# stuff-BASIC.net
KiCad netlist of a schematic drawn in EAGLE
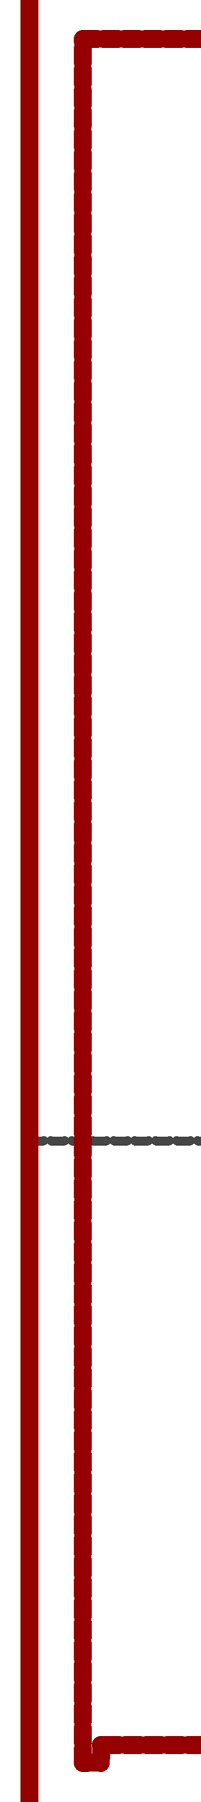
[diagram p0: schematic, sheet 1, part 1 of 2]
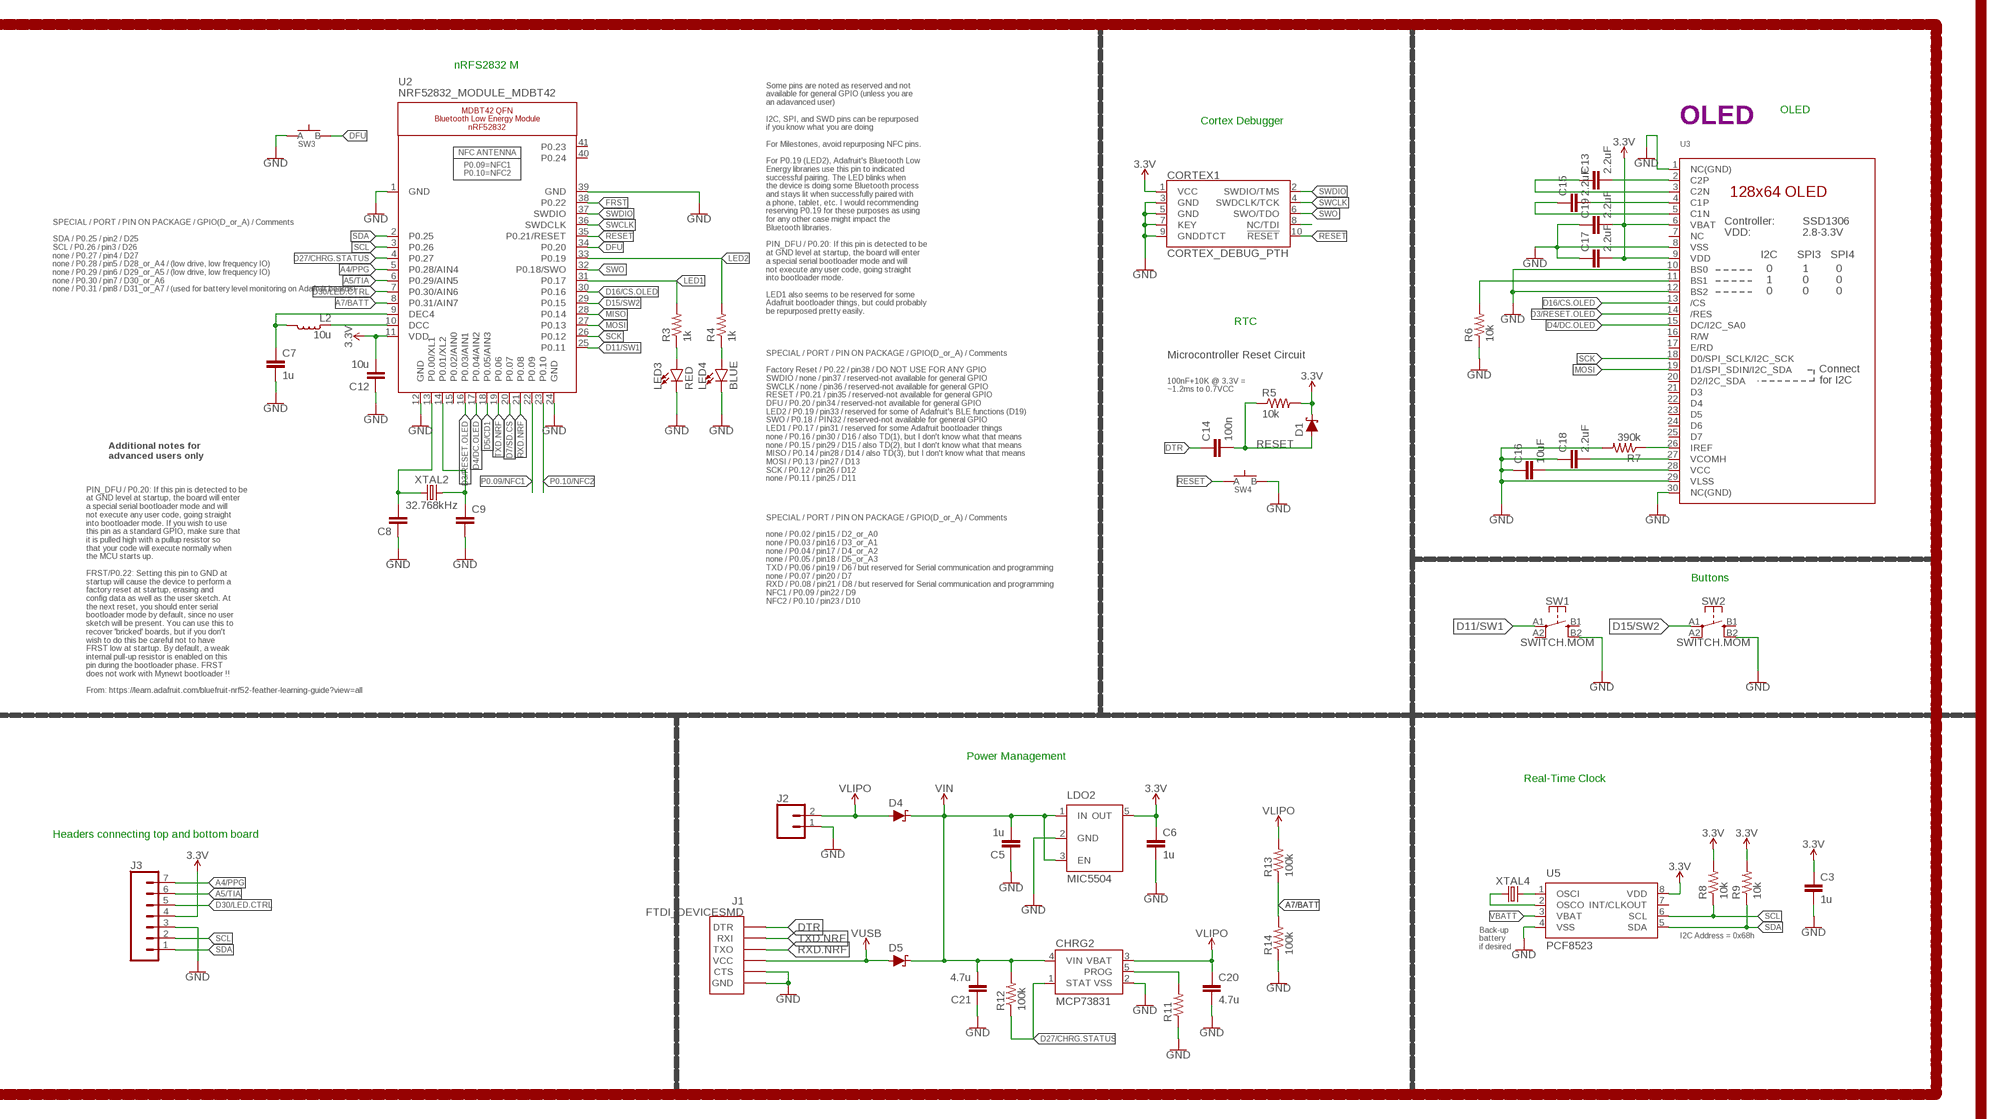
[diagram p1: schematic, sheet 1, part 2 of 2]

(export (version "E")
  (design (tool "Eeschema 10.0.6"))
  (components
    (comp (ref "C3")
      (value "1u")
      (footprint "eagle-import:C0603")
      (libsource (lib "eagle-import") (part "CAPACITOR0603"))
    )
    (comp (ref "C5")
      (value "1u")
      (footprint "eagle-import:C0603")
      (libsource (lib "eagle-import") (part "CAPACITOR0603"))
    )
    (comp (ref "C6")
      (value "1u")
      (footprint "eagle-import:C0603")
      (libsource (lib "eagle-import") (part "CAPACITOR0603"))
    )
    (comp (ref "C7")
      (value "1u")
      (footprint "eagle-import:C0603")
      (libsource (lib "eagle-import") (part "CAPACITOR0603"))
    )
    (comp (ref "C8")
      (value "CAPACITOR0603")
      (footprint "eagle-import:C0603")
      (libsource (lib "eagle-import") (part "CAPACITOR0603"))
    )
    (comp (ref "C9")
      (value "CAPACITOR0603")
      (footprint "eagle-import:C0603")
      (libsource (lib "eagle-import") (part "CAPACITOR0603"))
    )
    (comp (ref "C12")
      (value "10u")
      (footprint "eagle-import:C0805")
      (libsource (lib "eagle-import") (part "CAPACITOR0805"))
    )
    (comp (ref "C13")
      (value "2.2uF")
      (footprint "eagle-import:C0603")
      (libsource (lib "eagle-import") (part "CAPACITOR0603"))
    )
    (comp (ref "C14")
      (value "100n")
      (footprint "eagle-import:C0603")
      (libsource (lib "eagle-import") (part "CAPACITOR0603"))
    )
    (comp (ref "C15")
      (value "2.2uF")
      (footprint "eagle-import:C0603")
      (libsource (lib "eagle-import") (part "CAPACITOR0603"))
    )
    (comp (ref "C16")
      (value "10uF")
      (footprint "eagle-import:C0603")
      (libsource (lib "eagle-import") (part "CAPACITOR0603"))
    )
    (comp (ref "C17")
      (value "2.2uF")
      (footprint "eagle-import:C0603")
      (libsource (lib "eagle-import") (part "CAPACITOR0603"))
    )
    (comp (ref "C18")
      (value "2.2uF")
      (footprint "eagle-import:C0603")
      (libsource (lib "eagle-import") (part "CAPACITOR0603"))
    )
    (comp (ref "C19")
      (value "2.2uF")
      (footprint "eagle-import:C0603")
      (libsource (lib "eagle-import") (part "CAPACITOR0603"))
    )
    (comp (ref "C20")
      (value "4.7u")
      (footprint "eagle-import:C0603")
      (libsource (lib "eagle-import") (part "CAPACITOR0603"))
    )
    (comp (ref "C21")
      (value "4.7u")
      (footprint "eagle-import:C0603")
      (libsource (lib "eagle-import") (part "CAPACITOR0603"))
    )
    (comp (ref "CHRG2")
      (value "MCP73831")
      (footprint "eagle-import:SOT23-5")
      (libsource (lib "eagle-import") (part "MCP73831"))
    )
    (comp (ref "CORTEX1")
      (value "CORTEX_DEBUG_PTH")
      (footprint "eagle-import:2X5-PTH-1.27MM")
      (libsource (lib "eagle-import") (part "CORTEX_DEBUG_PTH"))
    )
    (comp (ref "D1")
      (value "SCHOTTKY-USC")
      (footprint "eagle-import:USC")
      (libsource (lib "eagle-import") (part "SCHOTTKY-USC"))
    )
    (comp (ref "D4")
      (value "SCHOTTKY-USC")
      (footprint "eagle-import:USC")
      (libsource (lib "eagle-import") (part "SCHOTTKY-USC"))
    )
    (comp (ref "D5")
      (value "SCHOTTKY-USC")
      (footprint "eagle-import:USC")
      (libsource (lib "eagle-import") (part "SCHOTTKY-USC"))
    )
    (comp (ref "J1")
      (value "FTDI_DEVICESMD")
      (footprint "eagle-import:FTDI-SMD")
      (libsource (lib "eagle-import") (part "FTDI_DEVICESMD"))
    )
    (comp (ref "J2")
      (value "CONN_02")
      (footprint "eagle-import:1X02")
      (libsource (lib "eagle-import") (part "CONN_02"))
    )
    (comp (ref "J3")
      (value "CONN_07-1.27MM")
      (footprint "eagle-import:1X07_1.27MM")
      (libsource (lib "eagle-import") (part "CONN_07-1.27MM"))
    )
    (comp (ref "L2")
      (value "10u")
      (footprint "eagle-import:L0603")
      (libsource (lib "eagle-import") (part "INDUCTOR0603"))
    )
    (comp (ref "LDO2")
      (value "MIC5504")
      (footprint "eagle-import:SOT23-5")
      (libsource (lib "eagle-import") (part "MIC5504"))
    )
    (comp (ref "LED3")
      (value "RED")
      (footprint "eagle-import:LED-0603")
      (libsource (lib "eagle-import") (part "LED0603"))
    )
    (comp (ref "LED4")
      (value "BLUE")
      (footprint "eagle-import:LED-0603")
      (libsource (lib "eagle-import") (part "LED0603"))
    )
    (comp (ref "R3")
      (value "1k")
      (footprint "eagle-import:R0603")
      (libsource (lib "eagle-import") (part "RESISTOR0603"))
    )
    (comp (ref "R4")
      (value "1k")
      (footprint "eagle-import:R0603")
      (libsource (lib "eagle-import") (part "RESISTOR0603"))
    )
    (comp (ref "R5")
      (value "10k")
      (footprint "eagle-import:R0603")
      (libsource (lib "eagle-import") (part "RESISTOR0603"))
    )
    (comp (ref "R6")
      (value "10k")
      (footprint "eagle-import:R0603")
      (libsource (lib "eagle-import") (part "RESISTOR0603"))
    )
    (comp (ref "R7")
      (value "390k")
      (footprint "eagle-import:R0603")
      (libsource (lib "eagle-import") (part "RESISTOR0603"))
    )
    (comp (ref "R8")
      (value "10k")
      (footprint "eagle-import:R0603")
      (libsource (lib "eagle-import") (part "RESISTOR0603"))
    )
    (comp (ref "R9")
      (value "10k")
      (footprint "eagle-import:R0603")
      (libsource (lib "eagle-import") (part "RESISTOR0603"))
    )
    (comp (ref "R11")
      (value "RESISTOR0603")
      (footprint "eagle-import:R0603")
      (libsource (lib "eagle-import") (part "RESISTOR0603"))
    )
    (comp (ref "R12")
      (value "100k")
      (footprint "eagle-import:R0603")
      (libsource (lib "eagle-import") (part "RESISTOR0603"))
    )
    (comp (ref "R13")
      (value "100k")
      (footprint "eagle-import:R0603")
      (libsource (lib "eagle-import") (part "RESISTOR0603"))
    )
    (comp (ref "R14")
      (value "100k")
      (footprint "eagle-import:R0603")
      (libsource (lib "eagle-import") (part "RESISTOR0603"))
    )
    (comp (ref "SW1")
      (value "SWITCH.MOM")
      (footprint "eagle-import:TACTILE_SWITCH_SMD_6.2MM_TALL")
      (libsource (lib "eagle-import") (part "SWITCH.MOM"))
    )
    (comp (ref "SW2")
      (value "SWITCH.MOM")
      (footprint "eagle-import:TACTILE_SWITCH_SMD_6.2MM_TALL")
      (libsource (lib "eagle-import") (part "SWITCH.MOM"))
    )
    (comp (ref "SW3")
      (value "SPST-PTS830GG140-COPY.1-3")
      (footprint "eagle-import:BUTTON-GULLWING")
      (libsource (lib "eagle-import") (part "SPST-PTS830GG140-COPY.1-3"))
    )
    (comp (ref "SW4")
      (value "SPST-PTS830GG140-COPY.1-3")
      (footprint "eagle-import:BUTTON-GULLWING")
      (libsource (lib "eagle-import") (part "SPST-PTS830GG140-COPY.1-3"))
    )
    (comp (ref "U2")
      (value "NRF52832_MODULE_MDBT42")
      (footprint "eagle-import:BLE_MODULE_RAYTAC_MDBT42")
      (libsource (lib "eagle-import") (part "NRF52832_MODULE_MDBT42"))
    )
    (comp (ref "U3")
      (value "DISP_OLED_UG-2864HSWEG01-NO-WRAPAROUND")
      (footprint "eagle-import:UG-2864HSWEG01_0.96IN_NO-WRAPAROUND")
      (libsource (lib "eagle-import") (part "DISP_OLED_UG-2864HSWEG01-NO-WRAPAROUND"))
    )
    (comp (ref "U5")
      (value "PCF8523")
      (footprint "eagle-import:SO8")
      (libsource (lib "eagle-import") (part "PCF8523"))
    )
    (comp (ref "XTAL2")
      (value "32.768kHz")
      (footprint "eagle-import:2-SMD.NOLEAD.2.0MMTO1.2MM")
      (libsource (lib "eagle-import") (part "CRYSTALECS-.327-12.5-12-C-TR"))
    )
    (comp (ref "XTAL4")
      (value "32.7680kHz")
      (footprint "eagle-import:2-SMD.NOLEAD.2.0MMTO1.2MM")
      (fields (field (name "FREQ") "32.7680KHZ"))
      (libsource (lib "eagle-import") (part "CRYSTALECS-.327-12.5-12-C-TR"))
    )
  )
  (nets
    (net (code "1") (name "3.3V") (class "Default")
      (node (ref "C12") (pin "2") (pinfunction "2_2") (pintype "passive"))
      (node (ref "C17") (pin "2") (pinfunction "2_2") (pintype "passive"))
      (node (ref "C19") (pin "2") (pinfunction "2_2") (pintype "passive"))
      (node (ref "C3") (pin "1") (pinfunction "1_1") (pintype "passive"))
      (node (ref "C6") (pin "1") (pinfunction "1_1") (pintype "passive"))
      (node (ref "CORTEX1") (pin "1") (pinfunction "VCC_1") (pintype "bidirectional"))
      (node (ref "D1") (pin "-") (pinfunction "C_-") (pintype "passive"))
      (node (ref "J3") (pin "4") (pinfunction "4_4") (pintype "passive"))
      (node (ref "LDO2") (pin "5") (pinfunction "OUT_5") (pintype "bidirectional"))
      (node (ref "R5") (pin "2") (pinfunction "2_2") (pintype "passive"))
      (node (ref "R8") (pin "2") (pinfunction "2_2") (pintype "passive"))
      (node (ref "R9") (pin "2") (pinfunction "2_2") (pintype "passive"))
      (node (ref "U2") (pin "11") (pinfunction "VDD_11") (pintype "bidirectional"))
      (node (ref "U3") (pin "6") (pinfunction "VBAT_6") (pintype "input"))
      (node (ref "U3") (pin "9") (pinfunction "VDD_9") (pintype "power_in"))
      (node (ref "U5") (pin "8") (pinfunction "VDD_8") (pintype "power_in"))
    )
    (net (code "2") (name "A4{slash}PPG") (class "Default")
      (node (ref "J3") (pin "7") (pinfunction "7_7") (pintype "passive"))
      (node (ref "U2") (pin "5") (pinfunction "P0.28/AIN4_5") (pintype "bidirectional"))
    )
    (net (code "3") (name "A5{slash}TIA") (class "Default")
      (node (ref "J3") (pin "6") (pinfunction "6_6") (pintype "passive"))
      (node (ref "U2") (pin "6") (pinfunction "P0.29/AIN5_6") (pintype "bidirectional"))
    )
    (net (code "4") (name "A7{slash}BATT") (class "Default")
      (node (ref "R13") (pin "1") (pinfunction "1_1") (pintype "passive"))
      (node (ref "R14") (pin "2") (pinfunction "2_2") (pintype "passive"))
      (node (ref "U2") (pin "8") (pinfunction "P0.31/AIN7_8") (pintype "bidirectional"))
    )
    (net (code "5") (name "D3{slash}RESET.OLED") (class "Default")
      (node (ref "U2") (pin "16") (pinfunction "P0.03/AIN1_16") (pintype "bidirectional"))
      (node (ref "U3") (pin "14") (pinfunction "/RES_14") (pintype "input"))
    )
    (net (code "6") (name "D4{slash}DC.OLED") (class "Default")
      (node (ref "U2") (pin "17") (pinfunction "P0.04/AIN2_17") (pintype "bidirectional"))
      (node (ref "U3") (pin "15") (pinfunction "DC/I2C_SA0_15") (pintype "input"))
    )
    (net (code "7") (name "D5{slash}CD1") (class "Default")
      (node (ref "U2") (pin "18") (pinfunction "P0.05/AIN3_18") (pintype "bidirectional"))
    )
    (net (code "8") (name "D7{slash}SD.CS") (class "Default")
      (node (ref "U2") (pin "20") (pinfunction "P0.07_20") (pintype "bidirectional"))
    )
    (net (code "9") (name "D11{slash}SW1") (class "Default")
      (node (ref "SW1") (pin "A1") (pinfunction "1_A1") (pintype "passive"))
      (node (ref "U2") (pin "25") (pinfunction "P0.11_25") (pintype "bidirectional"))
    )
    (net (code "10") (name "D15{slash}SW2") (class "Default")
      (node (ref "SW2") (pin "A1") (pinfunction "1_A1") (pintype "passive"))
      (node (ref "U2") (pin "29") (pinfunction "P0.15_29") (pintype "bidirectional"))
    )
    (net (code "11") (name "D16{slash}CS.OLED") (class "Default")
      (node (ref "U2") (pin "30") (pinfunction "P0.16_30") (pintype "bidirectional"))
      (node (ref "U3") (pin "13") (pinfunction "/CS_13") (pintype "input"))
    )
    (net (code "12") (name "D27{slash}CHRG.STATUS") (class "Default")
      (node (ref "CHRG2") (pin "1") (pinfunction "STAT_1") (pintype "output"))
      (node (ref "R12") (pin "1") (pinfunction "1_1") (pintype "passive"))
      (node (ref "U2") (pin "4") (pinfunction "P0.27_4") (pintype "bidirectional"))
    )
    (net (code "13") (name "D30{slash}LED.CTRL") (class "Default")
      (node (ref "J3") (pin "5") (pinfunction "5_5") (pintype "passive"))
      (node (ref "U2") (pin "7") (pinfunction "P0.30/AIN6_7") (pintype "bidirectional"))
    )
    (net (code "14") (name "DFU") (class "Default")
      (node (ref "SW3") (pin "3") (pinfunction "B_3") (pintype "bidirectional"))
      (node (ref "U2") (pin "34") (pinfunction "P0.20_34") (pintype "bidirectional"))
    )
    (net (code "15") (name "DTR") (class "Default")
      (node (ref "C14") (pin "1") (pinfunction "1_1") (pintype "passive"))
      (node (ref "J1") (pin "DTR") (pinfunction "DTR_DTR") (pintype "bidirectional"))
    )
    (net (code "16") (name "FRST") (class "Default")
      (node (ref "U2") (pin "38") (pinfunction "P0.22_38") (pintype "bidirectional"))
    )
    (net (code "17") (name "GND") (class "Default")
      (node (ref "C12") (pin "1") (pinfunction "1_1") (pintype "passive"))
      (node (ref "C16") (pin "1") (pinfunction "1_1") (pintype "passive"))
      (node (ref "C17") (pin "1") (pinfunction "1_1") (pintype "passive"))
      (node (ref "C18") (pin "1") (pinfunction "1_1") (pintype "passive"))
      (node (ref "C19") (pin "1") (pinfunction "1_1") (pintype "passive"))
      (node (ref "C20") (pin "2") (pinfunction "2_2") (pintype "passive"))
      (node (ref "C21") (pin "1") (pinfunction "1_1") (pintype "passive"))
      (node (ref "C3") (pin "2") (pinfunction "2_2") (pintype "passive"))
      (node (ref "C5") (pin "1") (pinfunction "1_1") (pintype "passive"))
      (node (ref "C6") (pin "2") (pinfunction "2_2") (pintype "passive"))
      (node (ref "C7") (pin "2") (pinfunction "2_2") (pintype "passive"))
      (node (ref "C8") (pin "1") (pinfunction "1_1") (pintype "passive"))
      (node (ref "C9") (pin "2") (pinfunction "2_2") (pintype "passive"))
      (node (ref "CHRG2") (pin "2") (pinfunction "VSS_2") (pintype "power_in"))
      (node (ref "CORTEX1") (pin "3") (pinfunction "GND_3") (pintype "bidirectional"))
      (node (ref "CORTEX1") (pin "5") (pinfunction "GND_5") (pintype "bidirectional"))
      (node (ref "CORTEX1") (pin "7") (pinfunction "KEY_7") (pintype "bidirectional"))
      (node (ref "CORTEX1") (pin "9") (pinfunction "GNDDTCT_9") (pintype "bidirectional"))
      (node (ref "J1") (pin "CTS") (pinfunction "CTS_CTS") (pintype "bidirectional"))
      (node (ref "J1") (pin "GND") (pinfunction "GND_GND") (pintype "bidirectional"))
      (node (ref "J2") (pin "1") (pinfunction "1_1") (pintype "passive"))
      (node (ref "J3") (pin "3") (pinfunction "3_3") (pintype "passive"))
      (node (ref "LDO2") (pin "2") (pinfunction "GND_2") (pintype "bidirectional"))
      (node (ref "LED3") (pin "C") (pinfunction "C_C") (pintype "passive"))
      (node (ref "LED4") (pin "C") (pinfunction "C_C") (pintype "passive"))
      (node (ref "R11") (pin "1") (pinfunction "1_1") (pintype "passive"))
      (node (ref "R14") (pin "1") (pinfunction "1_1") (pintype "passive"))
      (node (ref "R6") (pin "1") (pinfunction "1_1") (pintype "passive"))
      (node (ref "R7") (pin "2") (pinfunction "2_2") (pintype "passive"))
      (node (ref "SW1") (pin "B2") (pinfunction "4_B2") (pintype "passive"))
      (node (ref "SW2") (pin "B2") (pinfunction "4_B2") (pintype "passive"))
      (node (ref "SW3") (pin "1") (pinfunction "A_1") (pintype "bidirectional"))
      (node (ref "SW4") (pin "3") (pinfunction "B_3") (pintype "bidirectional"))
      (node (ref "U2") (pin "1") (pinfunction "GND_1") (pintype "bidirectional"))
      (node (ref "U2") (pin "12") (pinfunction "GND_12") (pintype "bidirectional"))
      (node (ref "U2") (pin "24") (pinfunction "GND_24") (pintype "bidirectional"))
      (node (ref "U2") (pin "39") (pinfunction "GND_39") (pintype "bidirectional"))
      (node (ref "U3") (pin "1") (pinfunction "NC(GND)_1") (pintype "input"))
      (node (ref "U3") (pin "10") (pinfunction "BS0_10") (pintype "input"))
      (node (ref "U3") (pin "12") (pinfunction "BS2_12") (pintype "input"))
      (node (ref "U3") (pin "29") (pinfunction "VLSS_29") (pintype "power_in"))
      (node (ref "U3") (pin "30") (pinfunction "NC(GND)_30") (pintype "input"))
      (node (ref "U3") (pin "8") (pinfunction "VSS_8") (pintype "power_in"))
      (node (ref "U5") (pin "4") (pinfunction "VSS_4") (pintype "power_in"))
    )
    (net (code "18") (name "LED1") (class "Default")
      (node (ref "R3") (pin "2") (pinfunction "2_2") (pintype "passive"))
      (node (ref "U2") (pin "31") (pinfunction "P0.17_31") (pintype "bidirectional"))
    )
    (net (code "19") (name "LED2") (class "Default")
      (node (ref "R4") (pin "2") (pinfunction "2_2") (pintype "passive"))
      (node (ref "U2") (pin "33") (pinfunction "P0.19_33") (pintype "bidirectional"))
    )
    (net (code "20") (name "MISO") (class "Default")
      (node (ref "U2") (pin "28") (pinfunction "P0.14_28") (pintype "bidirectional"))
    )
    (net (code "21") (name "MOSI") (class "Default")
      (node (ref "U2") (pin "27") (pinfunction "P0.13_27") (pintype "bidirectional"))
      (node (ref "U3") (pin "19") (pinfunction "D1/SPI_SDIN/I2C_SDA_19") (pintype "bidirectional"))
    )
    (net (code "22") (name "Net-(CHRG2-PROG)") (class "Default")
      (node (ref "CHRG2") (pin "5") (pinfunction "PROG_5") (pintype "input"))
      (node (ref "R11") (pin "2") (pinfunction "2_2") (pintype "passive"))
    )
    (net (code "23") (name "Net-(LED3-PadA)") (class "Default")
      (node (ref "LED3") (pin "A") (pinfunction "A_A") (pintype "passive"))
      (node (ref "R3") (pin "1") (pinfunction "1_1") (pintype "passive"))
    )
    (net (code "24") (name "Net-(LED4-PadA)") (class "Default")
      (node (ref "LED4") (pin "A") (pinfunction "A_A") (pintype "passive"))
      (node (ref "R4") (pin "1") (pinfunction "1_1") (pintype "passive"))
    )
    (net (code "25") (name "Net-(U2-DCC)") (class "Default")
      (node (ref "L2") (pin "1") (pinfunction "1_1") (pintype "passive"))
      (node (ref "U2") (pin "10") (pinfunction "DCC_10") (pintype "bidirectional"))
    )
    (net (code "26") (name "Net-(U2-DEC4)") (class "Default")
      (node (ref "C7") (pin "1") (pinfunction "1_1") (pintype "passive"))
      (node (ref "L2") (pin "2") (pinfunction "2_2") (pintype "passive"))
      (node (ref "U2") (pin "9") (pinfunction "DEC4_9") (pintype "bidirectional"))
    )
    (net (code "27") (name "Net-(U2-P0.00{slash}XL1)") (class "Default")
      (node (ref "C8") (pin "2") (pinfunction "2_2") (pintype "passive"))
      (node (ref "U2") (pin "13") (pinfunction "P0.00/XL1_13") (pintype "bidirectional"))
      (node (ref "XTAL2") (pin "P$1") (pinfunction "1_P$1") (pintype "passive"))
    )
    (net (code "28") (name "Net-(U2-P0.01{slash}XL2)") (class "Default")
      (node (ref "C9") (pin "1") (pinfunction "1_1") (pintype "passive"))
      (node (ref "U2") (pin "14") (pinfunction "P0.01/XL2_14") (pintype "bidirectional"))
      (node (ref "XTAL2") (pin "P$2") (pinfunction "2_P$2") (pintype "passive"))
    )
    (net (code "29") (name "Net-(U3-BS1)") (class "Default")
      (node (ref "R6") (pin "2") (pinfunction "2_2") (pintype "passive"))
      (node (ref "U3") (pin "11") (pinfunction "BS1_11") (pintype "input"))
    )
    (net (code "30") (name "Net-(U3-C1N)") (class "Default")
      (node (ref "C15") (pin "1") (pinfunction "1_1") (pintype "passive"))
      (node (ref "U3") (pin "5") (pinfunction "C1N_5") (pintype "input"))
    )
    (net (code "31") (name "Net-(U3-C1P)") (class "Default")
      (node (ref "C15") (pin "2") (pinfunction "2_2") (pintype "passive"))
      (node (ref "U3") (pin "4") (pinfunction "C1P_4") (pintype "input"))
    )
    (net (code "32") (name "Net-(U3-C2N)") (class "Default")
      (node (ref "C13") (pin "1") (pinfunction "1_1") (pintype "passive"))
      (node (ref "U3") (pin "3") (pinfunction "C2N_3") (pintype "input"))
    )
    (net (code "33") (name "Net-(U3-C2P)") (class "Default")
      (node (ref "C13") (pin "2") (pinfunction "2_2") (pintype "passive"))
      (node (ref "U3") (pin "2") (pinfunction "C2P_2") (pintype "input"))
    )
    (net (code "34") (name "Net-(U3-IREF)") (class "Default")
      (node (ref "R7") (pin "1") (pinfunction "1_1") (pintype "passive"))
      (node (ref "U3") (pin "26") (pinfunction "IREF_26") (pintype "input"))
    )
    (net (code "35") (name "Net-(U3-VCC)") (class "Default")
      (node (ref "C16") (pin "2") (pinfunction "2_2") (pintype "passive"))
      (node (ref "U3") (pin "28") (pinfunction "VCC_28") (pintype "power_in"))
    )
    (net (code "36") (name "Net-(U3-VCOMH)") (class "Default")
      (node (ref "C18") (pin "2") (pinfunction "2_2") (pintype "passive"))
      (node (ref "U3") (pin "27") (pinfunction "VCOMH_27") (pintype "output"))
    )
    (net (code "37") (name "Net-(U5-OSCI)") (class "Default")
      (node (ref "U5") (pin "1") (pinfunction "OSCI_1") (pintype "bidirectional"))
      (node (ref "XTAL4") (pin "P$2") (pinfunction "2_P$2") (pintype "passive"))
    )
    (net (code "38") (name "Net-(U5-OSCO)") (class "Default")
      (node (ref "U5") (pin "2") (pinfunction "OSCO_2") (pintype "bidirectional"))
      (node (ref "XTAL4") (pin "P$1") (pinfunction "1_P$1") (pintype "passive"))
    )
    (net (code "39") (name "P0.09{slash}NFC1") (class "Default")
      (node (ref "U2") (pin "22") (pinfunction "P0.09_22") (pintype "bidirectional"))
    )
    (net (code "40") (name "P0.10{slash}NFC2") (class "Default")
      (node (ref "U2") (pin "23") (pinfunction "P0.10_23") (pintype "bidirectional"))
    )
    (net (code "41") (name "RESET") (class "Default")
      (node (ref "C14") (pin "2") (pinfunction "2_2") (pintype "passive"))
      (node (ref "CORTEX1") (pin "10") (pinfunction "~{RESET}_10") (pintype "bidirectional"))
      (node (ref "D1") (pin "+") (pinfunction "A_+") (pintype "passive"))
      (node (ref "R5") (pin "1") (pinfunction "1_1") (pintype "passive"))
      (node (ref "SW4") (pin "1") (pinfunction "A_1") (pintype "bidirectional"))
      (node (ref "U2") (pin "35") (pinfunction "P0.21/RESET_35") (pintype "bidirectional"))
    )
    (net (code "42") (name "RXD.NRF") (class "Default")
      (node (ref "J1") (pin "TXO") (pinfunction "TXO_TXO") (pintype "bidirectional"))
      (node (ref "U2") (pin "21") (pinfunction "P0.08_21") (pintype "bidirectional"))
    )
    (net (code "43") (name "SCK") (class "Default")
      (node (ref "U2") (pin "26") (pinfunction "P0.12_26") (pintype "bidirectional"))
      (node (ref "U3") (pin "18") (pinfunction "D0/SPI_SCLK/I2C_SCK_18") (pintype "bidirectional"))
    )
    (net (code "44") (name "SCL") (class "Default")
      (node (ref "J3") (pin "2") (pinfunction "2_2") (pintype "passive"))
      (node (ref "R8") (pin "1") (pinfunction "1_1") (pintype "passive"))
      (node (ref "U2") (pin "3") (pinfunction "P0.26_3") (pintype "bidirectional"))
      (node (ref "U5") (pin "6") (pinfunction "SCL_6") (pintype "bidirectional"))
    )
    (net (code "45") (name "SDA") (class "Default")
      (node (ref "J3") (pin "1") (pinfunction "1_1") (pintype "passive"))
      (node (ref "R9") (pin "1") (pinfunction "1_1") (pintype "passive"))
      (node (ref "U2") (pin "2") (pinfunction "P0.25_2") (pintype "bidirectional"))
      (node (ref "U5") (pin "5") (pinfunction "SDA_5") (pintype "bidirectional"))
    )
    (net (code "46") (name "SWCLK") (class "Default")
      (node (ref "CORTEX1") (pin "4") (pinfunction "SWDCLK/TCK_4") (pintype "bidirectional"))
      (node (ref "U2") (pin "36") (pinfunction "SWDCLK_36") (pintype "bidirectional"))
    )
    (net (code "47") (name "SWDIO") (class "Default")
      (node (ref "CORTEX1") (pin "2") (pinfunction "SWDIO/TMS_2") (pintype "bidirectional"))
      (node (ref "U2") (pin "37") (pinfunction "SWDIO_37") (pintype "bidirectional"))
    )
    (net (code "48") (name "SWO") (class "Default")
      (node (ref "CORTEX1") (pin "6") (pinfunction "SWO/TDO_6") (pintype "bidirectional"))
      (node (ref "U2") (pin "32") (pinfunction "P0.18/SWO_32") (pintype "bidirectional"))
    )
    (net (code "49") (name "TXD.NRF") (class "Default")
      (node (ref "J1") (pin "RXI") (pinfunction "RXI_RXI") (pintype "bidirectional"))
      (node (ref "U2") (pin "19") (pinfunction "P0.06_19") (pintype "bidirectional"))
    )
    (net (code "50") (name "VBATT") (class "Default")
      (node (ref "U5") (pin "3") (pinfunction "VBAT_3") (pintype "power_in"))
    )
    (net (code "51") (name "VIN") (class "Default")
      (node (ref "C21") (pin "2") (pinfunction "2_2") (pintype "passive"))
      (node (ref "C5") (pin "2") (pinfunction "2_2") (pintype "passive"))
      (node (ref "CHRG2") (pin "4") (pinfunction "VIN_4") (pintype "power_in"))
      (node (ref "D4") (pin "-") (pinfunction "C_-") (pintype "passive"))
      (node (ref "D5") (pin "-") (pinfunction "C_-") (pintype "passive"))
      (node (ref "LDO2") (pin "1") (pinfunction "IN_1") (pintype "bidirectional"))
      (node (ref "LDO2") (pin "3") (pinfunction "EN_3") (pintype "bidirectional"))
      (node (ref "R12") (pin "2") (pinfunction "2_2") (pintype "passive"))
    )
    (net (code "52") (name "VLIPO") (class "Default")
      (node (ref "C20") (pin "1") (pinfunction "1_1") (pintype "passive"))
      (node (ref "CHRG2") (pin "3") (pinfunction "VBAT_3") (pintype "power_in"))
      (node (ref "D4") (pin "+") (pinfunction "A_+") (pintype "passive"))
      (node (ref "J2") (pin "2") (pinfunction "2_2") (pintype "passive"))
      (node (ref "R13") (pin "2") (pinfunction "2_2") (pintype "passive"))
    )
    (net (code "53") (name "VUSB") (class "Default")
      (node (ref "D5") (pin "+") (pinfunction "A_+") (pintype "passive"))
      (node (ref "J1") (pin "VCC") (pinfunction "VCC_VCC") (pintype "bidirectional"))
    )
    (net (code "54") (name "unconnected-(CORTEX1-NC{slash}TDI-Pad8)") (class "Default")
      (node (ref "CORTEX1") (pin "8") (pinfunction "NC/TDI_8") (pintype "bidirectional"))
    )
    (net (code "55") (name "unconnected-(SW1-2-PadA2)") (class "Default")
      (node (ref "SW1") (pin "A2") (pinfunction "2_A2") (pintype "passive"))
    )
    (net (code "56") (name "unconnected-(SW1-3-PadB1)") (class "Default")
      (node (ref "SW1") (pin "B1") (pinfunction "3_B1") (pintype "passive"))
    )
    (net (code "57") (name "unconnected-(SW2-2-PadA2)") (class "Default")
      (node (ref "SW2") (pin "A2") (pinfunction "2_A2") (pintype "passive"))
    )
    (net (code "58") (name "unconnected-(SW2-3-PadB1)") (class "Default")
      (node (ref "SW2") (pin "B1") (pinfunction "3_B1") (pintype "passive"))
    )
    (net (code "59") (name "unconnected-(U2-P0.02{slash}AIN0-Pad15)") (class "Default")
      (node (ref "U2") (pin "15") (pinfunction "P0.02/AIN0_15") (pintype "bidirectional"))
    )
    (net (code "60") (name "unconnected-(U2-P0.23-Pad41)") (class "Default")
      (node (ref "U2") (pin "41") (pinfunction "P0.23_41") (pintype "bidirectional"))
    )
    (net (code "61") (name "unconnected-(U2-P0.24-Pad40)") (class "Default")
      (node (ref "U2") (pin "40") (pinfunction "P0.24_40") (pintype "bidirectional"))
    )
    (net (code "62") (name "unconnected-(U3-D2{slash}I2C_SDA-Pad20)") (class "Default")
      (node (ref "U3") (pin "20") (pinfunction "D2/I2C_SDA_20") (pintype "bidirectional"))
    )
    (net (code "63") (name "unconnected-(U3-D3-Pad21)") (class "Default")
      (node (ref "U3") (pin "21") (pinfunction "D3_21") (pintype "bidirectional"))
    )
    (net (code "64") (name "unconnected-(U3-D4-Pad22)") (class "Default")
      (node (ref "U3") (pin "22") (pinfunction "D4_22") (pintype "bidirectional"))
    )
    (net (code "65") (name "unconnected-(U3-D5-Pad23)") (class "Default")
      (node (ref "U3") (pin "23") (pinfunction "D5_23") (pintype "bidirectional"))
    )
    (net (code "66") (name "unconnected-(U3-D6-Pad24)") (class "Default")
      (node (ref "U3") (pin "24") (pinfunction "D6_24") (pintype "bidirectional"))
    )
    (net (code "67") (name "unconnected-(U3-D7-Pad25)") (class "Default")
      (node (ref "U3") (pin "25") (pinfunction "D7_25") (pintype "bidirectional"))
    )
    (net (code "68") (name "unconnected-(U3-E{slash}RD-Pad17)") (class "Default")
      (node (ref "U3") (pin "17") (pinfunction "E/RD_17") (pintype "input"))
    )
    (net (code "69") (name "unconnected-(U3-NC-Pad7)") (class "Default")
      (node (ref "U3") (pin "7") (pinfunction "NC_7") (pintype "no_connect"))
    )
    (net (code "70") (name "unconnected-(U3-R{slash}W-Pad16)") (class "Default")
      (node (ref "U3") (pin "16") (pinfunction "R/W_16") (pintype "input"))
    )
    (net (code "71") (name "unconnected-(U5-INT{slash}CLKOUT-Pad7)") (class "Default")
      (node (ref "U5") (pin "7") (pinfunction "INT/CLKOUT_7") (pintype "bidirectional"))
    )
  )
)
